# Analog_Digital_Converter.net
KiCad netlist of a schematic drawn in Altium Designer
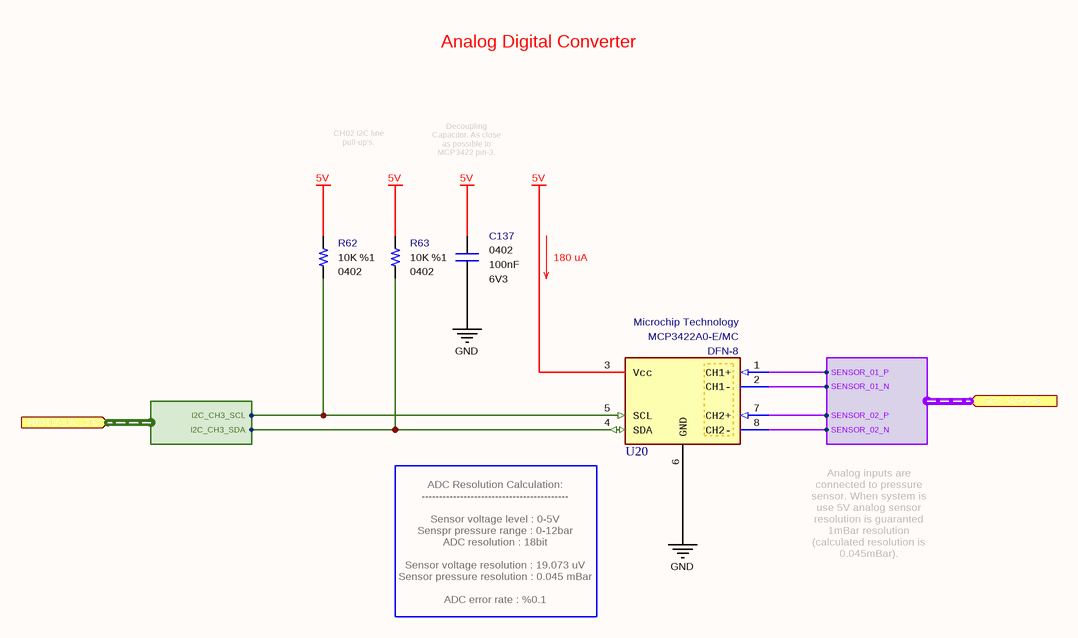
[diagram p0: Analog Digital Converter.SchDoc]

(export (version "E")
  (design (tool "Eeschema 10.0.6"))
  (components
    (comp (ref "C137")
      (value "100nF")
      (footprint "CAPACITOR_0402")
      (description "Capacitor - 100nF [0402-6V3] (Ceramic)")
      (fields
        (field (name "TOLERANCE") "%10")
        (field (name "CASE") "0402")
        (field (name "VOLTAGE") "6V3")
        (field (name "MANUFACTURER PART NUMBER") "04026D104KAT4A")
      )
      (libsource (lib "Ovoo_Library") (part "Capacitor - 100nF [0402-6V3]"))
    )
    (comp (ref "R62")
      (value "10K")
      (footprint "RESISTOR_0402")
      (description "Thick Film Resistors - SMD 1/16 W 10 Kohms 1%")
      (fields
        (field (name "TOLERANCE") "%1")
        (field (name "CASE") "0402")
        (field (name "MANUFACTURER PART NUMBER") "CRCW040210K0FKED")
        (field (name "MOUSER PART NUMBER") "71-CRCW0402-10K-E3")
      )
      (libsource (lib "Ovoo_Library") (part "Resistor - 10K"))
    )
    (comp (ref "R63")
      (value "10K")
      (footprint "RESISTOR_0402")
      (description "Thick Film Resistors - SMD 1/16 W 10 Kohms 1%")
      (fields
        (field (name "TOLERANCE") "%1")
        (field (name "CASE") "0402")
        (field (name "MANUFACTURER PART NUMBER") "CRCW040210K0FKED")
        (field (name "MOUSER PART NUMBER") "71-CRCW0402-10K-E3")
      )
      (libsource (lib "Ovoo_Library") (part "Resistor - 10K"))
    )
    (comp (ref "U20")
      (value "Analog to Digital Converters - ADC")
      (footprint "DFN-8")
      (description "Analog to Digital Converters - ADC 18B delta-sigma ADC dual Ch 4sps")
      (fields
        (field (name "CASE") "DFN-8")
        (field (name "MOUSER PART NUMBER") "579-MCP3422A0-E/MC")
        (field (name "MANUFACTURER PART NUMBER") "MCP3422A0-E/MC")
        (field (name "MANUFACTURER NAME") "Microchip Technology")
      )
      (libsource (lib "Ovoo_Library") (part "IC - MCP3422"))
    )
  )
  (nets
    (net (code "3") (name "/I2C_CH3_SCL") (class "Default")
      (node (ref "R62") (pin "1") (pinfunction "1_1") (pintype "passive"))
      (node (ref "U20") (pin "5") (pinfunction "SCL_5") (pintype "input"))
    )
    (net (code "4") (name "/I2C_CH3_SDA") (class "Default")
      (node (ref "R63") (pin "1") (pinfunction "1_1") (pintype "passive"))
      (node (ref "U20") (pin "4") (pinfunction "SDA_4") (pintype "bidirectional"))
    )
    (net (code "5") (name "/SENSOR_01_N") (class "Default")
      (node (ref "U20") (pin "2") (pinfunction "CH1-_2") (pintype "passive"))
    )
    (net (code "6") (name "/SENSOR_01_P") (class "Default")
      (node (ref "U20") (pin "1") (pinfunction "CH1+_1") (pintype "input"))
    )
    (net (code "7") (name "/SENSOR_02_N") (class "Default")
      (node (ref "U20") (pin "8") (pinfunction "CH2-_8") (pintype "passive"))
    )
    (net (code "8") (name "/SENSOR_02_P") (class "Default")
      (node (ref "U20") (pin "7") (pinfunction "CH2+_7") (pintype "input"))
    )
    (net (code "11") (name "5V") (class "Default")
      (node (ref "C137") (pin "2") (pinfunction "2_2") (pintype "passive"))
      (node (ref "R62") (pin "2") (pinfunction "2_2") (pintype "passive"))
      (node (ref "R63") (pin "2") (pinfunction "2_2") (pintype "passive"))
      (node (ref "U20") (pin "3") (pinfunction "Vcc_3") (pintype "power_in"))
    )
    (net (code "12") (name "GND") (class "Default")
      (node (ref "C137") (pin "1") (pinfunction "1_1") (pintype "passive"))
      (node (ref "U20") (pin "6") (pinfunction "GND_6") (pintype "power_in"))
    )
  )
)
